# HLM1_SLAVE.net
KiCad netlist of a schematic drawn in EAGLE
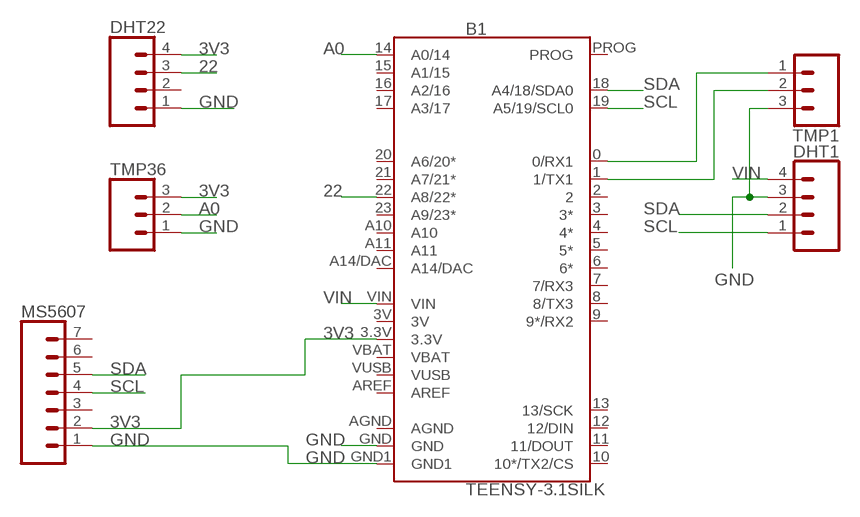
[diagram p0: schematic, sheet 1]

(export (version "E")
  (design (tool "Eeschema 10.0.6"))
  (components
    (comp (ref "B1")
      (value "TEENSY-3.1SILK")
      (footprint "eagle-import:TEENSY-3.1")
      (libsource (lib "eagle-import") (part "TEENSY-3.1SILK"))
    )
    (comp (ref "DHT1")
      (value "CONN_04")
      (footprint "eagle-import:1X04")
      (libsource (lib "eagle-import") (part "CONN_04"))
    )
    (comp (ref "DHT22")
      (value "CONN_04")
      (footprint "eagle-import:1X04")
      (libsource (lib "eagle-import") (part "CONN_04"))
    )
    (comp (ref "MS5607")
      (value "CONN_07")
      (footprint "eagle-import:1X07")
      (libsource (lib "eagle-import") (part "CONN_07"))
    )
    (comp (ref "TMP1")
      (value "CONN_03")
      (footprint "eagle-import:1X03")
      (libsource (lib "eagle-import") (part "CONN_03"))
    )
    (comp (ref "TMP36")
      (value "CONN_03")
      (footprint "eagle-import:1X03")
      (libsource (lib "eagle-import") (part "CONN_03"))
    )
  )
  (nets
    (net (code "1") (name "/3V") (class "Default")
      (node (ref "B1") (pin "3V") (pinfunction "3V_3V") (pintype "power_in"))
    )
    (net (code "2") (name "/3V3") (class "Default")
      (node (ref "B1") (pin "3.3V") (pinfunction "3.3V_3.3V") (pintype "power_in"))
      (node (ref "DHT22") (pin "4") (pinfunction "4_4") (pintype "passive"))
      (node (ref "MS5607") (pin "2") (pinfunction "2_2") (pintype "passive"))
      (node (ref "TMP36") (pin "3") (pinfunction "3_3") (pintype "passive"))
    )
    (net (code "3") (name "/22") (class "Default")
      (node (ref "B1") (pin "22") (pinfunction "A8/22*_22") (pintype "bidirectional"))
      (node (ref "DHT22") (pin "3") (pinfunction "3_3") (pintype "passive"))
    )
    (net (code "4") (name "/A0") (class "Default")
      (node (ref "B1") (pin "14") (pinfunction "A0/14_14") (pintype "bidirectional"))
      (node (ref "TMP36") (pin "2") (pinfunction "2_2") (pintype "passive"))
    )
    (net (code "5") (name "/AGND") (class "Default")
      (node (ref "B1") (pin "AGND") (pinfunction "AGND_AGND") (pintype "power_in"))
    )
    (net (code "6") (name "/GND") (class "Default")
      (node (ref "B1") (pin "GND") (pinfunction "GND_GND") (pintype "power_in"))
      (node (ref "B1") (pin "GND1") (pinfunction "GND1_GND1") (pintype "power_in"))
      (node (ref "DHT1") (pin "3") (pinfunction "3_3") (pintype "passive"))
      (node (ref "DHT22") (pin "1") (pinfunction "1_1") (pintype "passive"))
      (node (ref "MS5607") (pin "1") (pinfunction "1_1") (pintype "passive"))
      (node (ref "TMP1") (pin "3") (pinfunction "3_3") (pintype "passive"))
      (node (ref "TMP36") (pin "1") (pinfunction "1_1") (pintype "passive"))
    )
    (net (code "7") (name "/SCL") (class "Default")
      (node (ref "B1") (pin "19") (pinfunction "A5/19/SCL0_19") (pintype "bidirectional"))
      (node (ref "DHT1") (pin "1") (pinfunction "1_1") (pintype "passive"))
      (node (ref "MS5607") (pin "4") (pinfunction "4_4") (pintype "passive"))
    )
    (net (code "8") (name "/SDA") (class "Default")
      (node (ref "B1") (pin "18") (pinfunction "A4/18/SDA0_18") (pintype "bidirectional"))
      (node (ref "DHT1") (pin "2") (pinfunction "2_2") (pintype "passive"))
      (node (ref "MS5607") (pin "5") (pinfunction "5_5") (pintype "passive"))
    )
    (net (code "9") (name "/VBAT") (class "Default")
      (node (ref "B1") (pin "VBAT") (pinfunction "VBAT_VBAT") (pintype "power_in"))
    )
    (net (code "10") (name "/VIN") (class "Default")
      (node (ref "B1") (pin "VIN") (pinfunction "VIN_VIN") (pintype "power_in"))
      (node (ref "DHT1") (pin "4") (pinfunction "4_4") (pintype "passive"))
    )
    (net (code "11") (name "/VUSB") (class "Default")
      (node (ref "B1") (pin "VUSB") (pinfunction "VUSB_VUSB") (pintype "power_in"))
    )
    (net (code "12") (name "Net-(B1-0{slash}RX1)") (class "Default")
      (node (ref "B1") (pin "0") (pinfunction "0/RX1_0") (pintype "bidirectional"))
      (node (ref "TMP1") (pin "1") (pinfunction "1_1") (pintype "passive"))
    )
    (net (code "13") (name "Net-(B1-1{slash}TX1)") (class "Default")
      (node (ref "B1") (pin "1") (pinfunction "1/TX1_1") (pintype "bidirectional"))
      (node (ref "TMP1") (pin "2") (pinfunction "2_2") (pintype "passive"))
    )
    (net (code "14") (name "unconnected-(B1-3*-Pad3)") (class "Default")
      (node (ref "B1") (pin "3") (pinfunction "3*_3") (pintype "bidirectional"))
    )
    (net (code "15") (name "unconnected-(B1-4*-Pad4)") (class "Default")
      (node (ref "B1") (pin "4") (pinfunction "4*_4") (pintype "bidirectional"))
    )
    (net (code "16") (name "unconnected-(B1-5*-Pad5)") (class "Default")
      (node (ref "B1") (pin "5") (pinfunction "5*_5") (pintype "bidirectional"))
    )
    (net (code "17") (name "unconnected-(B1-6*-Pad6)") (class "Default")
      (node (ref "B1") (pin "6") (pinfunction "6*_6") (pintype "bidirectional"))
    )
    (net (code "18") (name "unconnected-(B1-7{slash}RX3-Pad7)") (class "Default")
      (node (ref "B1") (pin "7") (pinfunction "7/RX3_7") (pintype "bidirectional"))
    )
    (net (code "19") (name "unconnected-(B1-8{slash}TX3-Pad8)") (class "Default")
      (node (ref "B1") (pin "8") (pinfunction "8/TX3_8") (pintype "bidirectional"))
    )
    (net (code "20") (name "unconnected-(B1-9*{slash}RX2-Pad9)") (class "Default")
      (node (ref "B1") (pin "9") (pinfunction "9*/RX2_9") (pintype "bidirectional"))
    )
    (net (code "21") (name "unconnected-(B1-10*{slash}TX2{slash}CS-Pad10)") (class "Default")
      (node (ref "B1") (pin "10") (pinfunction "10*/TX2/CS_10") (pintype "bidirectional"))
    )
    (net (code "22") (name "unconnected-(B1-11{slash}DOUT-Pad11)") (class "Default")
      (node (ref "B1") (pin "11") (pinfunction "11/DOUT_11") (pintype "bidirectional"))
    )
    (net (code "23") (name "unconnected-(B1-12{slash}DIN-Pad12)") (class "Default")
      (node (ref "B1") (pin "12") (pinfunction "12/DIN_12") (pintype "bidirectional"))
    )
    (net (code "24") (name "unconnected-(B1-13{slash}SCK-Pad13)") (class "Default")
      (node (ref "B1") (pin "13") (pinfunction "13/SCK_13") (pintype "bidirectional"))
    )
    (net (code "25") (name "unconnected-(B1-A1{slash}15-Pad15)") (class "Default")
      (node (ref "B1") (pin "15") (pinfunction "A1/15_15") (pintype "bidirectional"))
    )
    (net (code "26") (name "unconnected-(B1-A2{slash}16-Pad16)") (class "Default")
      (node (ref "B1") (pin "16") (pinfunction "A2/16_16") (pintype "bidirectional"))
    )
    (net (code "27") (name "unconnected-(B1-A3{slash}17-Pad17)") (class "Default")
      (node (ref "B1") (pin "17") (pinfunction "A3/17_17") (pintype "bidirectional"))
    )
    (net (code "28") (name "unconnected-(B1-A6{slash}20*-Pad20)") (class "Default")
      (node (ref "B1") (pin "20") (pinfunction "A6/20*_20") (pintype "bidirectional"))
    )
    (net (code "29") (name "unconnected-(B1-A7{slash}21*-Pad21)") (class "Default")
      (node (ref "B1") (pin "21") (pinfunction "A7/21*_21") (pintype "bidirectional"))
    )
    (net (code "30") (name "unconnected-(B1-A9{slash}23*-Pad23)") (class "Default")
      (node (ref "B1") (pin "23") (pinfunction "A9/23*_23") (pintype "bidirectional"))
    )
    (net (code "31") (name "unconnected-(B1-Pad2)") (class "Default")
      (node (ref "B1") (pin "2") (pinfunction "2_2") (pintype "bidirectional"))
    )
    (net (code "32") (name "unconnected-(B1-PadA10)") (class "Default")
      (node (ref "B1") (pin "A10") (pinfunction "A10_A10") (pintype "bidirectional"))
    )
    (net (code "33") (name "unconnected-(B1-PadA11)") (class "Default")
      (node (ref "B1") (pin "A11") (pinfunction "A11_A11") (pintype "bidirectional"))
    )
    (net (code "34") (name "unconnected-(B1-PadA14{slash}DAC)") (class "Default")
      (node (ref "B1") (pin "A14/DAC") (pinfunction "A14/DAC_A14/DAC") (pintype "bidirectional"))
    )
    (net (code "35") (name "unconnected-(B1-PadAREF)") (class "Default")
      (node (ref "B1") (pin "AREF") (pinfunction "AREF_AREF") (pintype "bidirectional"))
    )
    (net (code "36") (name "unconnected-(B1-PadPROG)") (class "Default")
      (node (ref "B1") (pin "PROG") (pinfunction "PROG_PROG") (pintype "bidirectional"))
    )
    (net (code "37") (name "unconnected-(DHT22-Pad2)") (class "Default")
      (node (ref "DHT22") (pin "2") (pinfunction "2_2") (pintype "passive"))
    )
    (net (code "38") (name "unconnected-(MS5607-Pad3)") (class "Default")
      (node (ref "MS5607") (pin "3") (pinfunction "3_3") (pintype "passive"))
    )
    (net (code "39") (name "unconnected-(MS5607-Pad6)") (class "Default")
      (node (ref "MS5607") (pin "6") (pinfunction "6_6") (pintype "passive"))
    )
    (net (code "40") (name "unconnected-(MS5607-Pad7)") (class "Default")
      (node (ref "MS5607") (pin "7") (pinfunction "7_7") (pintype "passive"))
    )
  )
)
